# ME433_HW2.net
KiCad netlist of a schematic drawn in EAGLE
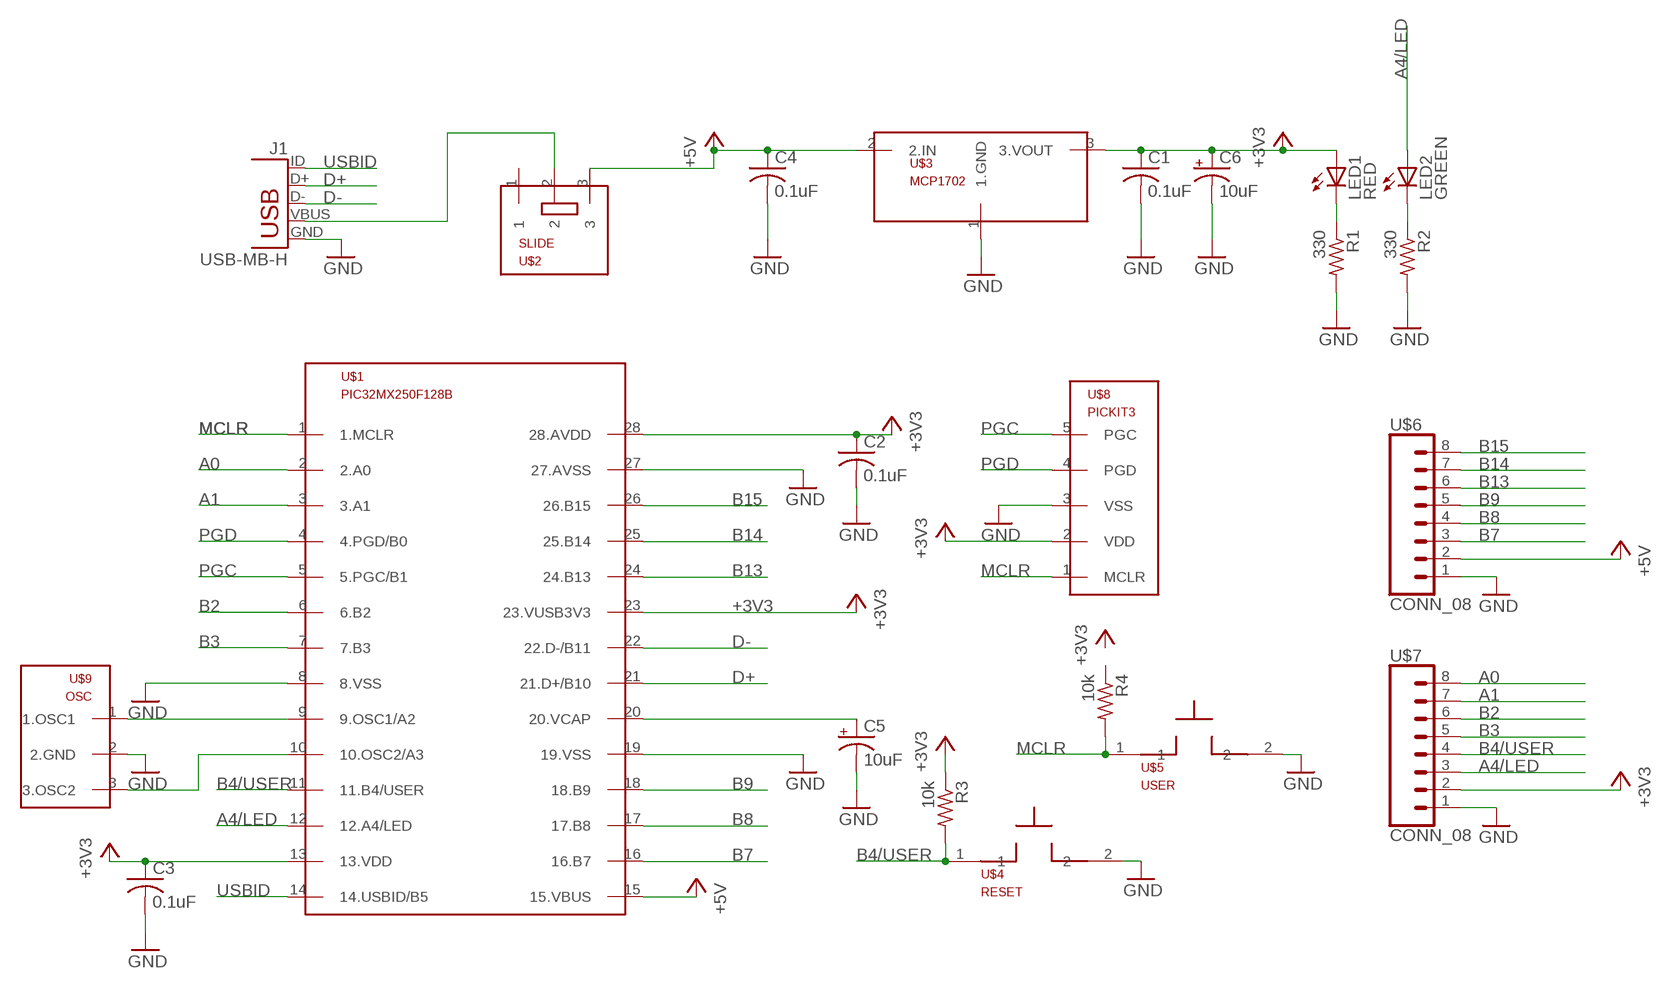
[diagram p0: schematic, sheet 1]

(export (version "E")
  (design (tool "Eeschema 10.0.6"))
  (components
    (comp (ref "C1")
      (value "0.1uF")
      (footprint "eagle-import:C025-025X050")
      (libsource (lib "eagle-import") (part "C-US025-025X050"))
    )
    (comp (ref "C2")
      (value "0.1uF")
      (footprint "eagle-import:C025-025X050")
      (libsource (lib "eagle-import") (part "C-US025-025X050"))
    )
    (comp (ref "C3")
      (value "0.1uF")
      (footprint "eagle-import:C025-025X050")
      (libsource (lib "eagle-import") (part "C-US025-025X050"))
    )
    (comp (ref "C4")
      (value "0.1uF")
      (footprint "eagle-import:C025-025X050")
      (libsource (lib "eagle-import") (part "C-US025-025X050"))
    )
    (comp (ref "C5")
      (value "10uF")
      (footprint "eagle-import:B45181B")
      (libsource (lib "eagle-import") (part "CPOL-USB45181B"))
    )
    (comp (ref "C6")
      (value "10uF")
      (footprint "eagle-import:B45181B")
      (libsource (lib "eagle-import") (part "CPOL-USB45181B"))
    )
    (comp (ref "J1")
      (value "USB-MB-H")
      (footprint "eagle-import:USB-MB-H")
      (libsource (lib "eagle-import") (part "USB-MB-H"))
    )
    (comp (ref "LED1")
      (value "RED")
      (footprint "eagle-import:LED3MM")
      (libsource (lib "eagle-import") (part "LED3MM"))
    )
    (comp (ref "LED2")
      (value "GREEN")
      (footprint "eagle-import:LED3MM")
      (libsource (lib "eagle-import") (part "LED3MM"))
    )
    (comp (ref "R1")
      (value "330")
      (footprint "eagle-import:0207_10")
      (libsource (lib "eagle-import") (part "R-US_0207/10"))
    )
    (comp (ref "R2")
      (value "330")
      (footprint "eagle-import:0207_10")
      (libsource (lib "eagle-import") (part "R-US_0207/10"))
    )
    (comp (ref "R3")
      (value "10k")
      (footprint "eagle-import:0207_10")
      (libsource (lib "eagle-import") (part "R-US_0207/10"))
    )
    (comp (ref "R4")
      (value "10k")
      (footprint "eagle-import:0207_10")
      (libsource (lib "eagle-import") (part "R-US_0207/10"))
    )
    (comp (ref "U$1")
      (value "PIC32MX250F128B")
      (footprint "eagle-import:DIL28-3")
      (libsource (lib "eagle-import") (part "PIC32MX250F128B"))
    )
    (comp (ref "U$2")
      (value "SLIDE")
      (footprint "eagle-import:SLIDE")
      (libsource (lib "eagle-import") (part "SLIDE"))
    )
    (comp (ref "U$3")
      (value "MCP1702")
      (footprint "eagle-import:TO92")
      (libsource (lib "eagle-import") (part "MCP1702"))
    )
    (comp (ref "U$4")
      (value "RESET")
      (footprint "eagle-import:PB")
      (libsource (lib "eagle-import") (part "PB"))
    )
    (comp (ref "U$5")
      (value "USER")
      (footprint "eagle-import:PB")
      (libsource (lib "eagle-import") (part "PB"))
    )
    (comp (ref "U$6")
      (value "CONN_08")
      (footprint "eagle-import:1X08")
      (libsource (lib "eagle-import") (part "CONN_08"))
    )
    (comp (ref "U$7")
      (value "CONN_08")
      (footprint "eagle-import:1X08")
      (libsource (lib "eagle-import") (part "CONN_08"))
    )
    (comp (ref "U$8")
      (value "PICKIT3")
      (footprint "eagle-import:1X05")
      (libsource (lib "eagle-import") (part "PICKIT3"))
    )
    (comp (ref "U$9")
      (value "OSC")
      (footprint "eagle-import:OSC")
      (libsource (lib "eagle-import") (part "OSC"))
    )
  )
  (nets
    (net (code "1") (name "+3V3") (class "Default")
      (node (ref "C1") (pin "1") (pinfunction "1_1") (pintype "passive"))
      (node (ref "C2") (pin "1") (pinfunction "1_1") (pintype "passive"))
      (node (ref "C3") (pin "1") (pinfunction "1_1") (pintype "passive"))
      (node (ref "C6") (pin "+") (pinfunction "+_+") (pintype "passive"))
      (node (ref "LED1") (pin "A") (pinfunction "A_A") (pintype "passive"))
      (node (ref "R3") (pin "1") (pinfunction "1_1") (pintype "passive"))
      (node (ref "U$1") (pin "13") (pinfunction "13.VDD_13") (pintype "bidirectional"))
      (node (ref "U$1") (pin "23") (pinfunction "23.VUSB3V3_23") (pintype "bidirectional"))
      (node (ref "U$1") (pin "28") (pinfunction "28.AVDD_28") (pintype "bidirectional"))
      (node (ref "U$3") (pin "3") (pinfunction "3.VOUT_3") (pintype "bidirectional"))
      (node (ref "U$7") (pin "2") (pinfunction "2_2") (pintype "passive"))
      (node (ref "U$8") (pin "2") (pinfunction "VDD_2") (pintype "bidirectional"))
    )
    (net (code "2") (name "+5V") (class "Default")
      (node (ref "C4") (pin "1") (pinfunction "1_1") (pintype "passive"))
      (node (ref "U$1") (pin "15") (pinfunction "15.VBUS_15") (pintype "bidirectional"))
      (node (ref "U$2") (pin "3") (pinfunction "3_3") (pintype "bidirectional"))
      (node (ref "U$3") (pin "2") (pinfunction "2.IN_2") (pintype "bidirectional"))
      (node (ref "U$6") (pin "2") (pinfunction "2_2") (pintype "passive"))
    )
    (net (code "3") (name "/A0") (class "Default")
      (node (ref "U$1") (pin "2") (pinfunction "2.A0_2") (pintype "bidirectional"))
      (node (ref "U$7") (pin "8") (pinfunction "8_8") (pintype "passive"))
    )
    (net (code "4") (name "/A1") (class "Default")
      (node (ref "U$1") (pin "3") (pinfunction "3.A1_3") (pintype "bidirectional"))
      (node (ref "U$7") (pin "7") (pinfunction "7_7") (pintype "passive"))
    )
    (net (code "5") (name "/A4{slash}LED") (class "Default")
      (node (ref "LED2") (pin "A") (pinfunction "A_A") (pintype "passive"))
      (node (ref "U$1") (pin "12") (pinfunction "12.A4/LED_12") (pintype "bidirectional"))
      (node (ref "U$7") (pin "3") (pinfunction "3_3") (pintype "passive"))
    )
    (net (code "6") (name "/B2") (class "Default")
      (node (ref "U$1") (pin "6") (pinfunction "6.B2_6") (pintype "bidirectional"))
      (node (ref "U$7") (pin "6") (pinfunction "6_6") (pintype "passive"))
    )
    (net (code "7") (name "/B3") (class "Default")
      (node (ref "U$1") (pin "7") (pinfunction "7.B3_7") (pintype "bidirectional"))
      (node (ref "U$7") (pin "5") (pinfunction "5_5") (pintype "passive"))
    )
    (net (code "8") (name "/B4{slash}USER") (class "Default")
      (node (ref "R3") (pin "2") (pinfunction "2_2") (pintype "passive"))
      (node (ref "U$1") (pin "11") (pinfunction "11.B4/USER_11") (pintype "bidirectional"))
      (node (ref "U$4") (pin "1") (pinfunction "1_1") (pintype "bidirectional"))
      (node (ref "U$7") (pin "4") (pinfunction "4_4") (pintype "passive"))
    )
    (net (code "9") (name "/B7") (class "Default")
      (node (ref "U$1") (pin "16") (pinfunction "16.B7_16") (pintype "bidirectional"))
      (node (ref "U$6") (pin "3") (pinfunction "3_3") (pintype "passive"))
    )
    (net (code "10") (name "/B8") (class "Default")
      (node (ref "U$1") (pin "17") (pinfunction "17.B8_17") (pintype "bidirectional"))
      (node (ref "U$6") (pin "4") (pinfunction "4_4") (pintype "passive"))
    )
    (net (code "11") (name "/B9") (class "Default")
      (node (ref "U$1") (pin "18") (pinfunction "18.B9_18") (pintype "bidirectional"))
      (node (ref "U$6") (pin "5") (pinfunction "5_5") (pintype "passive"))
    )
    (net (code "12") (name "/B13") (class "Default")
      (node (ref "U$1") (pin "24") (pinfunction "24.B13_24") (pintype "bidirectional"))
      (node (ref "U$6") (pin "6") (pinfunction "6_6") (pintype "passive"))
    )
    (net (code "13") (name "/B14") (class "Default")
      (node (ref "U$1") (pin "25") (pinfunction "25.B14_25") (pintype "bidirectional"))
      (node (ref "U$6") (pin "7") (pinfunction "7_7") (pintype "passive"))
    )
    (net (code "14") (name "/B15") (class "Default")
      (node (ref "U$1") (pin "26") (pinfunction "26.B15_26") (pintype "bidirectional"))
      (node (ref "U$6") (pin "8") (pinfunction "8_8") (pintype "passive"))
    )
    (net (code "15") (name "/D+") (class "Default")
      (node (ref "J1") (pin "D+") (pinfunction "D+_D+") (pintype "bidirectional"))
      (node (ref "U$1") (pin "21") (pinfunction "21.D+/B10_21") (pintype "bidirectional"))
    )
    (net (code "16") (name "/D-") (class "Default")
      (node (ref "J1") (pin "D-") (pinfunction "D-_D-") (pintype "bidirectional"))
      (node (ref "U$1") (pin "22") (pinfunction "22.D-/B11_22") (pintype "bidirectional"))
    )
    (net (code "17") (name "/MCLR") (class "Default")
      (node (ref "R4") (pin "2") (pinfunction "2_2") (pintype "passive"))
      (node (ref "U$1") (pin "1") (pinfunction "1.MCLR_1") (pintype "bidirectional"))
      (node (ref "U$5") (pin "1") (pinfunction "1_1") (pintype "bidirectional"))
      (node (ref "U$8") (pin "1") (pinfunction "MCLR_1") (pintype "bidirectional"))
    )
    (net (code "18") (name "/PGC") (class "Default")
      (node (ref "U$1") (pin "5") (pinfunction "5.PGC/B1_5") (pintype "bidirectional"))
      (node (ref "U$8") (pin "5") (pinfunction "PGC_5") (pintype "bidirectional"))
    )
    (net (code "19") (name "/PGD") (class "Default")
      (node (ref "U$1") (pin "4") (pinfunction "4.PGD/B0_4") (pintype "bidirectional"))
      (node (ref "U$8") (pin "4") (pinfunction "PGD_4") (pintype "bidirectional"))
    )
    (net (code "20") (name "/USBID") (class "Default")
      (node (ref "J1") (pin "ID") (pinfunction "ID_ID") (pintype "bidirectional"))
      (node (ref "U$1") (pin "14") (pinfunction "14.USBID/B5_14") (pintype "bidirectional"))
    )
    (net (code "21") (name "GND") (class "Default")
      (node (ref "C1") (pin "2") (pinfunction "2_2") (pintype "passive"))
      (node (ref "C2") (pin "2") (pinfunction "2_2") (pintype "passive"))
      (node (ref "C3") (pin "2") (pinfunction "2_2") (pintype "passive"))
      (node (ref "C4") (pin "2") (pinfunction "2_2") (pintype "passive"))
      (node (ref "C5") (pin "-") (pinfunction "-_-") (pintype "passive"))
      (node (ref "C6") (pin "-") (pinfunction "-_-") (pintype "passive"))
      (node (ref "J1") (pin "GND") (pinfunction "GND_GND") (pintype "bidirectional"))
      (node (ref "R1") (pin "2") (pinfunction "2_2") (pintype "passive"))
      (node (ref "R2") (pin "2") (pinfunction "2_2") (pintype "passive"))
      (node (ref "U$1") (pin "19") (pinfunction "19.VSS_19") (pintype "bidirectional"))
      (node (ref "U$1") (pin "27") (pinfunction "27.AVSS_27") (pintype "bidirectional"))
      (node (ref "U$1") (pin "8") (pinfunction "8.VSS_8") (pintype "bidirectional"))
      (node (ref "U$3") (pin "1") (pinfunction "1.GND_1") (pintype "bidirectional"))
      (node (ref "U$4") (pin "2") (pinfunction "2_2") (pintype "bidirectional"))
      (node (ref "U$5") (pin "2") (pinfunction "2_2") (pintype "bidirectional"))
      (node (ref "U$6") (pin "1") (pinfunction "1_1") (pintype "passive"))
      (node (ref "U$7") (pin "1") (pinfunction "1_1") (pintype "passive"))
      (node (ref "U$8") (pin "3") (pinfunction "VSS_3") (pintype "bidirectional"))
      (node (ref "U$9") (pin "2") (pinfunction "2.GND_2") (pintype "bidirectional"))
    )
    (net (code "22") (name "Net-(J1-PadVBUS)") (class "Default")
      (node (ref "J1") (pin "VBUS") (pinfunction "VBUS_VBUS") (pintype "bidirectional"))
      (node (ref "U$2") (pin "2") (pinfunction "2_2") (pintype "bidirectional"))
    )
    (net (code "23") (name "Net-(LED1-C)") (class "Default")
      (node (ref "LED1") (pin "K") (pinfunction "C_K") (pintype "passive"))
      (node (ref "R1") (pin "1") (pinfunction "1_1") (pintype "passive"))
    )
    (net (code "24") (name "Net-(LED2-C)") (class "Default")
      (node (ref "LED2") (pin "K") (pinfunction "C_K") (pintype "passive"))
      (node (ref "R2") (pin "1") (pinfunction "1_1") (pintype "passive"))
    )
    (net (code "25") (name "Net-(U$1-9.OSC1{slash}A2)") (class "Default")
      (node (ref "U$1") (pin "9") (pinfunction "9.OSC1/A2_9") (pintype "bidirectional"))
      (node (ref "U$9") (pin "1") (pinfunction "1.OSC1_1") (pintype "bidirectional"))
    )
    (net (code "26") (name "Net-(U$1-10.OSC2{slash}A3)") (class "Default")
      (node (ref "U$1") (pin "10") (pinfunction "10.OSC2/A3_10") (pintype "bidirectional"))
      (node (ref "U$9") (pin "3") (pinfunction "3.OSC2_3") (pintype "bidirectional"))
    )
    (net (code "27") (name "Net-(U$1-20.VCAP)") (class "Default")
      (node (ref "C5") (pin "+") (pinfunction "+_+") (pintype "passive"))
      (node (ref "U$1") (pin "20") (pinfunction "20.VCAP_20") (pintype "bidirectional"))
    )
    (net (code "28") (name "unconnected-(R4-Pad1)") (class "Default")
      (node (ref "R4") (pin "1") (pinfunction "1_1") (pintype "passive"))
    )
    (net (code "29") (name "unconnected-(U$2-Pad1)") (class "Default")
      (node (ref "U$2") (pin "1") (pinfunction "1_1") (pintype "bidirectional"))
    )
  )
)
